# Shield.net
KiCad netlist of a schematic drawn in EAGLE
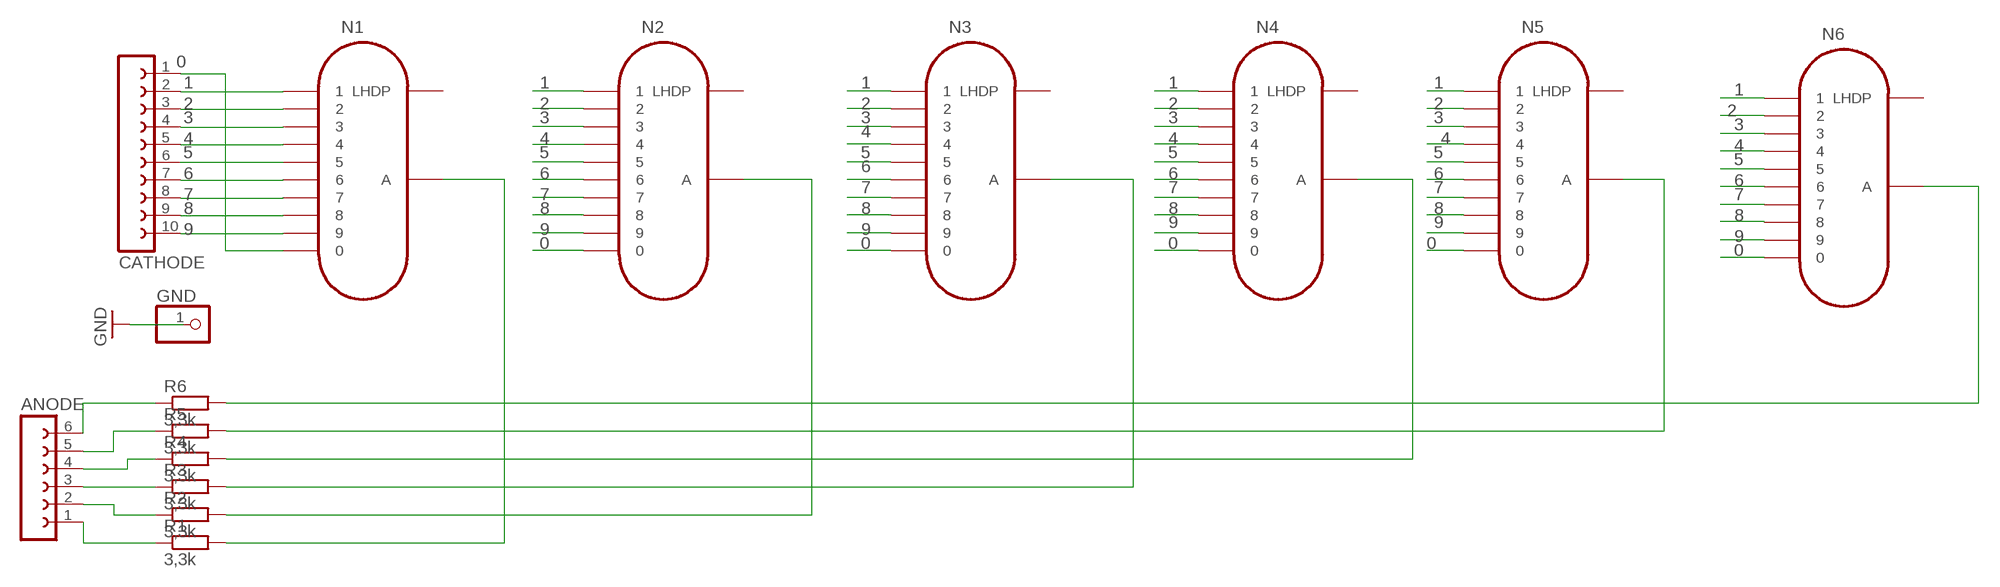
[diagram p0: schematic, sheet 1]

(export (version "E")
  (design (tool "Eeschema 10.0.6"))
  (components
    (comp (ref "ANODE")
      (value "FE06-1")
      (footprint "eagle-import:FE06")
      (libsource (lib "eagle-import") (part "FE06-1"))
    )
    (comp (ref "CATHODE")
      (value "FE10-1")
      (footprint "eagle-import:FE10")
      (libsource (lib "eagle-import") (part "FE10-1"))
    )
    (comp (ref "GND")
      (value "PINHD-1X1")
      (footprint "eagle-import:1X01")
      (libsource (lib "eagle-import") (part "PINHD-1X1"))
    )
    (comp (ref "N1")
      (value "IN-12B")
      (footprint "eagle-import:IN-12")
      (libsource (lib "eagle-import") (part "IN-12B"))
    )
    (comp (ref "N2")
      (value "IN-12B")
      (footprint "eagle-import:IN-12")
      (libsource (lib "eagle-import") (part "IN-12B"))
    )
    (comp (ref "N3")
      (value "IN-12B")
      (footprint "eagle-import:IN-12")
      (libsource (lib "eagle-import") (part "IN-12B"))
    )
    (comp (ref "N4")
      (value "IN-12B")
      (footprint "eagle-import:IN-12")
      (libsource (lib "eagle-import") (part "IN-12B"))
    )
    (comp (ref "N5")
      (value "IN-12B")
      (footprint "eagle-import:IN-12")
      (libsource (lib "eagle-import") (part "IN-12B"))
    )
    (comp (ref "N6")
      (value "IN-12B")
      (footprint "eagle-import:IN-12")
      (libsource (lib "eagle-import") (part "IN-12B"))
    )
    (comp (ref "R1")
      (value "3,3k")
      (footprint "eagle-import:0309_12")
      (libsource (lib "eagle-import") (part "R-EU_0309/12"))
    )
    (comp (ref "R2")
      (value "3,3k")
      (footprint "eagle-import:0309_12")
      (libsource (lib "eagle-import") (part "R-EU_0309/12"))
    )
    (comp (ref "R3")
      (value "3,3k")
      (footprint "eagle-import:0309_12")
      (libsource (lib "eagle-import") (part "R-EU_0309/12"))
    )
    (comp (ref "R4")
      (value "3,3k")
      (footprint "eagle-import:0309_12")
      (libsource (lib "eagle-import") (part "R-EU_0309/12"))
    )
    (comp (ref "R5")
      (value "3,3k")
      (footprint "eagle-import:0309_12")
      (libsource (lib "eagle-import") (part "R-EU_0309/12"))
    )
    (comp (ref "R6")
      (value "3,3k")
      (footprint "eagle-import:0309_12")
      (libsource (lib "eagle-import") (part "R-EU_0309/12"))
    )
  )
  (nets
    (net (code "1") (name "/0") (class "Default")
      (node (ref "CATHODE") (pin "1") (pinfunction "1_1") (pintype "passive"))
      (node (ref "N1") (pin "0") (pinfunction "0_0") (pintype "bidirectional"))
      (node (ref "N2") (pin "0") (pinfunction "0_0") (pintype "bidirectional"))
      (node (ref "N3") (pin "0") (pinfunction "0_0") (pintype "bidirectional"))
      (node (ref "N4") (pin "0") (pinfunction "0_0") (pintype "bidirectional"))
      (node (ref "N5") (pin "0") (pinfunction "0_0") (pintype "bidirectional"))
      (node (ref "N6") (pin "0") (pinfunction "0_0") (pintype "bidirectional"))
    )
    (net (code "2") (name "/1") (class "Default")
      (node (ref "CATHODE") (pin "2") (pinfunction "2_2") (pintype "passive"))
      (node (ref "N1") (pin "1") (pinfunction "1_1") (pintype "bidirectional"))
      (node (ref "N2") (pin "1") (pinfunction "1_1") (pintype "bidirectional"))
      (node (ref "N3") (pin "1") (pinfunction "1_1") (pintype "bidirectional"))
      (node (ref "N4") (pin "1") (pinfunction "1_1") (pintype "bidirectional"))
      (node (ref "N5") (pin "1") (pinfunction "1_1") (pintype "bidirectional"))
      (node (ref "N6") (pin "1") (pinfunction "1_1") (pintype "bidirectional"))
    )
    (net (code "3") (name "/2") (class "Default")
      (node (ref "CATHODE") (pin "3") (pinfunction "3_3") (pintype "passive"))
      (node (ref "N1") (pin "2") (pinfunction "2_2") (pintype "bidirectional"))
      (node (ref "N2") (pin "2") (pinfunction "2_2") (pintype "bidirectional"))
      (node (ref "N3") (pin "2") (pinfunction "2_2") (pintype "bidirectional"))
      (node (ref "N4") (pin "2") (pinfunction "2_2") (pintype "bidirectional"))
      (node (ref "N5") (pin "2") (pinfunction "2_2") (pintype "bidirectional"))
      (node (ref "N6") (pin "2") (pinfunction "2_2") (pintype "bidirectional"))
    )
    (net (code "4") (name "/3") (class "Default")
      (node (ref "CATHODE") (pin "4") (pinfunction "4_4") (pintype "passive"))
      (node (ref "N1") (pin "3") (pinfunction "3_3") (pintype "bidirectional"))
      (node (ref "N2") (pin "3") (pinfunction "3_3") (pintype "bidirectional"))
      (node (ref "N3") (pin "3") (pinfunction "3_3") (pintype "bidirectional"))
      (node (ref "N4") (pin "3") (pinfunction "3_3") (pintype "bidirectional"))
      (node (ref "N5") (pin "3") (pinfunction "3_3") (pintype "bidirectional"))
      (node (ref "N6") (pin "3") (pinfunction "3_3") (pintype "bidirectional"))
    )
    (net (code "5") (name "/4") (class "Default")
      (node (ref "CATHODE") (pin "5") (pinfunction "5_5") (pintype "passive"))
      (node (ref "N1") (pin "4") (pinfunction "4_4") (pintype "bidirectional"))
      (node (ref "N2") (pin "4") (pinfunction "4_4") (pintype "bidirectional"))
      (node (ref "N3") (pin "4") (pinfunction "4_4") (pintype "bidirectional"))
      (node (ref "N4") (pin "4") (pinfunction "4_4") (pintype "bidirectional"))
      (node (ref "N5") (pin "4") (pinfunction "4_4") (pintype "bidirectional"))
      (node (ref "N6") (pin "4") (pinfunction "4_4") (pintype "bidirectional"))
    )
    (net (code "6") (name "/5") (class "Default")
      (node (ref "CATHODE") (pin "6") (pinfunction "6_6") (pintype "passive"))
      (node (ref "N1") (pin "5") (pinfunction "5_5") (pintype "bidirectional"))
      (node (ref "N2") (pin "5") (pinfunction "5_5") (pintype "bidirectional"))
      (node (ref "N3") (pin "5") (pinfunction "5_5") (pintype "bidirectional"))
      (node (ref "N4") (pin "5") (pinfunction "5_5") (pintype "bidirectional"))
      (node (ref "N5") (pin "5") (pinfunction "5_5") (pintype "bidirectional"))
      (node (ref "N6") (pin "5") (pinfunction "5_5") (pintype "bidirectional"))
    )
    (net (code "7") (name "/6") (class "Default")
      (node (ref "CATHODE") (pin "7") (pinfunction "7_7") (pintype "passive"))
      (node (ref "N1") (pin "6") (pinfunction "6_6") (pintype "bidirectional"))
      (node (ref "N2") (pin "6") (pinfunction "6_6") (pintype "bidirectional"))
      (node (ref "N3") (pin "6") (pinfunction "6_6") (pintype "bidirectional"))
      (node (ref "N4") (pin "6") (pinfunction "6_6") (pintype "bidirectional"))
      (node (ref "N5") (pin "6") (pinfunction "6_6") (pintype "bidirectional"))
      (node (ref "N6") (pin "6") (pinfunction "6_6") (pintype "bidirectional"))
    )
    (net (code "8") (name "/7") (class "Default")
      (node (ref "CATHODE") (pin "8") (pinfunction "8_8") (pintype "passive"))
      (node (ref "N1") (pin "7") (pinfunction "7_7") (pintype "bidirectional"))
      (node (ref "N2") (pin "7") (pinfunction "7_7") (pintype "bidirectional"))
      (node (ref "N3") (pin "7") (pinfunction "7_7") (pintype "bidirectional"))
      (node (ref "N4") (pin "7") (pinfunction "7_7") (pintype "bidirectional"))
      (node (ref "N5") (pin "7") (pinfunction "7_7") (pintype "bidirectional"))
      (node (ref "N6") (pin "7") (pinfunction "7_7") (pintype "bidirectional"))
    )
    (net (code "9") (name "/8") (class "Default")
      (node (ref "CATHODE") (pin "9") (pinfunction "9_9") (pintype "passive"))
      (node (ref "N1") (pin "8") (pinfunction "8_8") (pintype "bidirectional"))
      (node (ref "N2") (pin "8") (pinfunction "8_8") (pintype "bidirectional"))
      (node (ref "N3") (pin "8") (pinfunction "8_8") (pintype "bidirectional"))
      (node (ref "N4") (pin "8") (pinfunction "8_8") (pintype "bidirectional"))
      (node (ref "N5") (pin "8") (pinfunction "8_8") (pintype "bidirectional"))
      (node (ref "N6") (pin "8") (pinfunction "8_8") (pintype "bidirectional"))
    )
    (net (code "10") (name "/9") (class "Default")
      (node (ref "CATHODE") (pin "10") (pinfunction "10_10") (pintype "passive"))
      (node (ref "N1") (pin "9") (pinfunction "9_9") (pintype "bidirectional"))
      (node (ref "N2") (pin "9") (pinfunction "9_9") (pintype "bidirectional"))
      (node (ref "N3") (pin "9") (pinfunction "9_9") (pintype "bidirectional"))
      (node (ref "N4") (pin "9") (pinfunction "9_9") (pintype "bidirectional"))
      (node (ref "N5") (pin "9") (pinfunction "9_9") (pintype "bidirectional"))
      (node (ref "N6") (pin "9") (pinfunction "9_9") (pintype "bidirectional"))
    )
    (net (code "11") (name "GND") (class "Default")
      (node (ref "GND") (pin "1") (pinfunction "1_1") (pintype "passive"))
    )
    (net (code "12") (name "Net-(ANODE-Pad1)") (class "Default")
      (node (ref "ANODE") (pin "1") (pinfunction "1_1") (pintype "passive"))
      (node (ref "R1") (pin "1") (pinfunction "1_1") (pintype "passive"))
    )
    (net (code "13") (name "Net-(ANODE-Pad2)") (class "Default")
      (node (ref "ANODE") (pin "2") (pinfunction "2_2") (pintype "passive"))
      (node (ref "R2") (pin "1") (pinfunction "1_1") (pintype "passive"))
    )
    (net (code "14") (name "Net-(ANODE-Pad3)") (class "Default")
      (node (ref "ANODE") (pin "3") (pinfunction "3_3") (pintype "passive"))
      (node (ref "R3") (pin "1") (pinfunction "1_1") (pintype "passive"))
    )
    (net (code "15") (name "Net-(ANODE-Pad4)") (class "Default")
      (node (ref "ANODE") (pin "4") (pinfunction "4_4") (pintype "passive"))
      (node (ref "R4") (pin "1") (pinfunction "1_1") (pintype "passive"))
    )
    (net (code "16") (name "Net-(ANODE-Pad5)") (class "Default")
      (node (ref "ANODE") (pin "5") (pinfunction "5_5") (pintype "passive"))
      (node (ref "R5") (pin "1") (pinfunction "1_1") (pintype "passive"))
    )
    (net (code "17") (name "Net-(ANODE-Pad6)") (class "Default")
      (node (ref "ANODE") (pin "6") (pinfunction "6_6") (pintype "passive"))
      (node (ref "R6") (pin "1") (pinfunction "1_1") (pintype "passive"))
    )
    (net (code "18") (name "Net-(N1-PadA)") (class "Default")
      (node (ref "N1") (pin "A") (pinfunction "A_A") (pintype "bidirectional"))
      (node (ref "R1") (pin "2") (pinfunction "2_2") (pintype "passive"))
    )
    (net (code "19") (name "Net-(N2-PadA)") (class "Default")
      (node (ref "N2") (pin "A") (pinfunction "A_A") (pintype "bidirectional"))
      (node (ref "R2") (pin "2") (pinfunction "2_2") (pintype "passive"))
    )
    (net (code "20") (name "Net-(N3-PadA)") (class "Default")
      (node (ref "N3") (pin "A") (pinfunction "A_A") (pintype "bidirectional"))
      (node (ref "R3") (pin "2") (pinfunction "2_2") (pintype "passive"))
    )
    (net (code "21") (name "Net-(N4-PadA)") (class "Default")
      (node (ref "N4") (pin "A") (pinfunction "A_A") (pintype "bidirectional"))
      (node (ref "R4") (pin "2") (pinfunction "2_2") (pintype "passive"))
    )
    (net (code "22") (name "Net-(N5-PadA)") (class "Default")
      (node (ref "N5") (pin "A") (pinfunction "A_A") (pintype "bidirectional"))
      (node (ref "R5") (pin "2") (pinfunction "2_2") (pintype "passive"))
    )
    (net (code "23") (name "Net-(N6-PadA)") (class "Default")
      (node (ref "N6") (pin "A") (pinfunction "A_A") (pintype "bidirectional"))
      (node (ref "R6") (pin "2") (pinfunction "2_2") (pintype "passive"))
    )
    (net (code "24") (name "unconnected-(N1-PadLHDP)") (class "Default")
      (node (ref "N1") (pin "LHDP") (pinfunction "LHDP_LHDP") (pintype "bidirectional"))
    )
    (net (code "25") (name "unconnected-(N2-PadLHDP)") (class "Default")
      (node (ref "N2") (pin "LHDP") (pinfunction "LHDP_LHDP") (pintype "bidirectional"))
    )
    (net (code "26") (name "unconnected-(N3-PadLHDP)") (class "Default")
      (node (ref "N3") (pin "LHDP") (pinfunction "LHDP_LHDP") (pintype "bidirectional"))
    )
    (net (code "27") (name "unconnected-(N4-PadLHDP)") (class "Default")
      (node (ref "N4") (pin "LHDP") (pinfunction "LHDP_LHDP") (pintype "bidirectional"))
    )
    (net (code "28") (name "unconnected-(N5-PadLHDP)") (class "Default")
      (node (ref "N5") (pin "LHDP") (pinfunction "LHDP_LHDP") (pintype "bidirectional"))
    )
    (net (code "29") (name "unconnected-(N6-PadLHDP)") (class "Default")
      (node (ref "N6") (pin "LHDP") (pinfunction "LHDP_LHDP") (pintype "bidirectional"))
    )
  )
)
